# SCH_ERV-controller_2026-01-07.net
KiCad netlist of a schematic drawn in EasyEDA
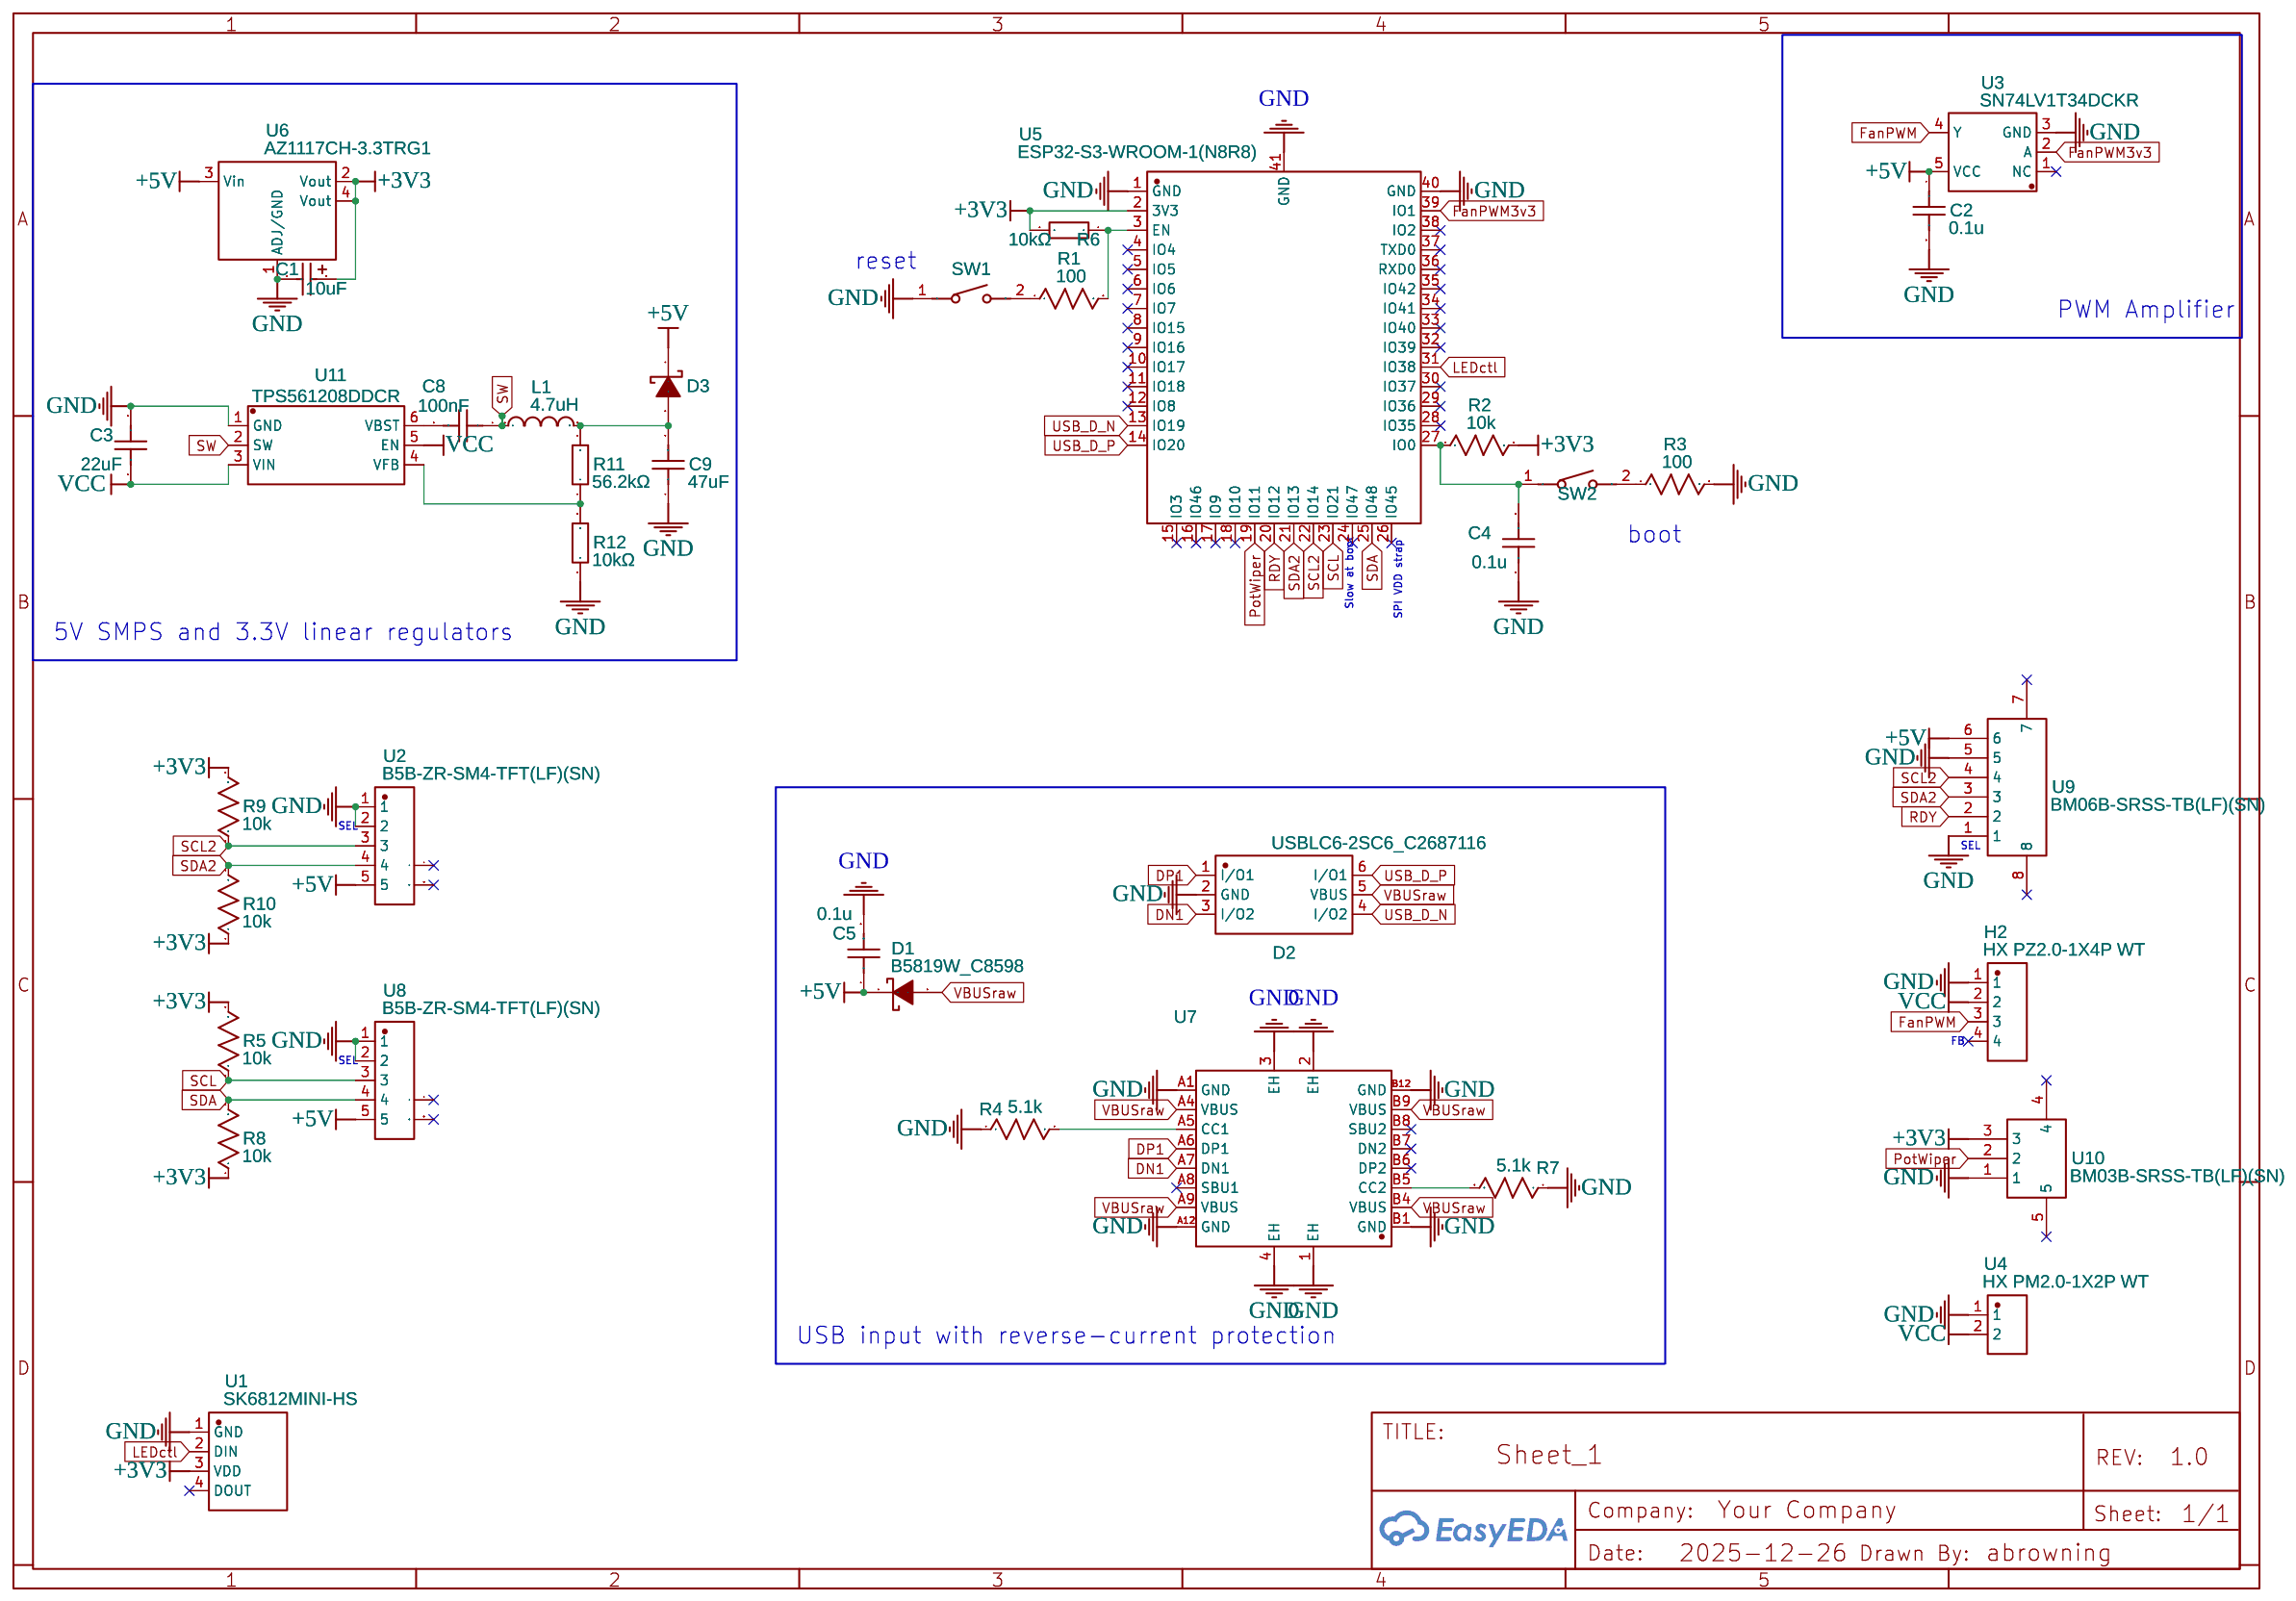
[diagram p0: schematic sheet]

(export (version "E")
  (design (tool "Eeschema 10.0.6"))
  (components
    (comp (ref "C1")
      (value "10uF")
      (fields (field (name "Manufacturer Part") "TAJA106K016RNJ") (field (name "Manufacturer") "Kyocera AVX"))
      (libsource (lib "") (part "TAJA106K016RNJ"))
    )
    (comp (ref "C2") (value "0.1u") (libsource (lib "") (part "C_0603_US")))
    (comp (ref "C3")
      (value "22uF")
      (fields
        (field (name "Manufacturer Part") "CL21A226MAQNNNE")
        (field (name "Manufacturer") "SAMSUNG(三星)")
      )
      (libsource (lib "") (part "CL21A226MAQNNNE"))
    )
    (comp (ref "C4") (value "0.1u") (libsource (lib "") (part "C_0603_US_1")))
    (comp (ref "C5") (value "0.1u") (libsource (lib "") (part "C_0603_US_1")))
    (comp (ref "C8")
      (value "100nF")
      (fields
        (field (name "Manufacturer Part") "CL05B104KO5NNNC")
        (field (name "Manufacturer") "SAMSUNG(三星)")
      )
      (libsource (lib "") (part "CL05B104KO5NNNC"))
    )
    (comp (ref "C9")
      (value "47uF")
      (fields
        (field (name "Manufacturer Part") "CL31A476MPHNNNE")
        (field (name "Manufacturer") "SAMSUNG(三星)")
      )
      (libsource (lib "") (part "CL31A476MPHNNNE"))
    )
    (comp (ref "D1")
      (value "B5819W_C8598")
      (fields (field (name "Manufacturer Part") "B5819W SL") (field (name "Manufacturer") "CJ(江苏长电/长晶)"))
      (libsource (lib "") (part "B5819W_C8598_1"))
    )
    (comp (ref "D2")
      (value "USBLC6-2SC6_C2687116")
      (fields (field (name "Manufacturer Part") "USBLC6-2SC6") (field (name "Manufacturer") "UMW(友台半导体)"))
      (libsource (lib "") (part "USBLC6-2SC6_C2687116"))
    )
    (comp (ref "D3")
      (value "B5819W_C8598")
      (fields (field (name "Manufacturer Part") "B5819W SL") (field (name "Manufacturer") "CJ(江苏长电/长晶)"))
      (libsource (lib "") (part "B5819W_C8598"))
    )
    (comp (ref "H2")
      (value "HX PZ2.0-1X4P WT")
      (fields
        (field (name "Manufacturer Part") "HX PZ2.0-1x4P WT")
        (field (name "Manufacturer") "hanxia(韩下)")
      )
      (libsource (lib "") (part "HX PZ2.0-1X4P WT"))
    )
    (comp (ref "L1")
      (value "4.7uH")
      (fields (field (name "Manufacturer Part") "LQM2HPN4R7MG0L") (field (name "Manufacturer") "muRata(村田)"))
      (libsource (lib "") (part "LQM2HPN4R7MG0L"))
    )
    (comp (ref "R1") (value "100") (libsource (lib "") (part "R_0603_US_1")))
    (comp (ref "R2") (value "10k") (libsource (lib "") (part "R_0603_US_1")))
    (comp (ref "R3") (value "100") (libsource (lib "") (part "R_0603_US_1")))
    (comp (ref "R4") (value "5.1k") (libsource (lib "") (part "R_0603_US_1")))
    (comp (ref "R5") (value "10k") (libsource (lib "") (part "R_0603_US_2")))
    (comp (ref "R6")
      (value "10kΩ")
      (fields
        (field (name "Manufacturer Part") "0402WGF1002TCE")
        (field (name "Manufacturer") "UNI-ROYAL(厚声)")
      )
      (libsource (lib "") (part "0402WGF1002TCE_1"))
    )
    (comp (ref "R7") (value "5.1k") (libsource (lib "") (part "R_0603_US")))
    (comp (ref "R8") (value "10k") (libsource (lib "") (part "R_0603_US_2")))
    (comp (ref "R9") (value "10k") (libsource (lib "") (part "R_0603_US_2")))
    (comp (ref "R10") (value "10k") (libsource (lib "") (part "R_0603_US_2")))
    (comp (ref "R11")
      (value "56.2kΩ")
      (fields (field (name "Manufacturer Part") "RC0402FR-0756K2L") (field (name "Manufacturer") "YAGEO(国巨)"))
      (libsource (lib "") (part "RC0402FR-0756K2L"))
    )
    (comp (ref "R12")
      (value "10kΩ")
      (fields
        (field (name "Manufacturer Part") "0402WGF1002TCE")
        (field (name "Manufacturer") "UNI-ROYAL(厚声)")
      )
      (libsource (lib "") (part "0402WGF1002TCE"))
    )
    (comp (ref "SW1")
      (value "TS-1088-AR02016")
      (fields (field (name "Manufacturer") "XUNPU(讯普)"))
      (libsource (lib "") (part "TS-1088-AR02016"))
    )
    (comp (ref "SW2")
      (value "TS-1088-AR02016")
      (fields (field (name "Manufacturer") "XUNPU(讯普)"))
      (libsource (lib "") (part "TS-1088-AR02016"))
    )
    (comp (ref "U1")
      (value "SK6812MINI-HS")
      (fields (field (name "Manufacturer") "欧思科光电"))
      (libsource (lib "") (part "SK6812MINI-HS"))
    )
    (comp (ref "U2")
      (value "B5B-ZR-SM4-TFT(LF)(SN)")
      (fields (field (name "Manufacturer") "JST"))
      (libsource (lib "") (part "B5B-ZR-SM4-TFT(LF)(SN)"))
    )
    (comp (ref "U3")
      (value "SN74LV1T34DCKR")
      (fields (field (name "Manufacturer") "TI(德州仪器)"))
      (libsource (lib "") (part "SN74LV1T34DCKR"))
    )
    (comp (ref "U4")
      (value "HX PM2.0-1X2P WT")
      (fields
        (field (name "Manufacturer Part") "HX PM2.0-1x2P WT")
        (field (name "Manufacturer") "hanxia(韩下)")
      )
      (libsource (lib "") (part "HX PM2.0-1X2P WT"))
    )
    (comp (ref "U5")
      (value "ESP32-S3-WROOM-1(N8R8)")
      (fields
        (field (name "Manufacturer Part") "ESP32-S3-WROOM-1-N8R8")
        (field (name "Manufacturer") "ESPRESSIF(乐鑫)")
      )
      (libsource (lib "") (part "ESP32-S3-WROOM-1(N8R8)"))
    )
    (comp (ref "U6")
      (value "AZ1117CH-3.3TRG1")
      (fields (field (name "Manufacturer") "DIODES(美台)"))
      (libsource (lib "") (part "AZ1117CH-3.3TRG1"))
    )
    (comp (ref "U7")
      (value "TYPE-C 16P LTH6.8")
      (fields (field (name "Manufacturer") "SHOU HAN(首韩)"))
      (libsource (lib "") (part "TYPE-C 16P LTH6.8"))
    )
    (comp (ref "U8")
      (value "B5B-ZR-SM4-TFT(LF)(SN)")
      (fields (field (name "Manufacturer") "JST"))
      (libsource (lib "") (part "B5B-ZR-SM4-TFT(LF)(SN)"))
    )
    (comp (ref "U9")
      (value "BM06B-SRSS-TB(LF)(SN)")
      (fields (field (name "Manufacturer") "JST"))
      (libsource (lib "") (part "BM06B-SRSS-TB(LF)(SN)"))
    )
    (comp (ref "U10")
      (value "BM03B-SRSS-TB(LF)(SN)")
      (fields (field (name "Manufacturer") "JST"))
      (libsource (lib "") (part "BM03B-SRSS-TB(LF)(SN)"))
    )
    (comp (ref "U11")
      (value "TPS561208DDCR")
      (fields (field (name "Manufacturer") "TI(德州仪器)"))
      (libsource (lib "") (part "TPS561208DDCR"))
    )
  )
  (nets
    (net (code "1") (name "+3V3") (class "Default")
      (node (ref "C1") (pin "1") (pinfunction "1_1") (pintype "input"))
      (node (ref "R10") (pin "1") (pinfunction "1_1") (pintype "unspecified"))
      (node (ref "R2") (pin "2") (pinfunction "2_2") (pintype "unspecified"))
      (node (ref "R5") (pin "2") (pinfunction "2_2") (pintype "unspecified"))
      (node (ref "R6") (pin "2") (pinfunction "2_2") (pintype "input"))
      (node (ref "R8") (pin "1") (pinfunction "1_1") (pintype "unspecified"))
      (node (ref "R9") (pin "2") (pinfunction "2_2") (pintype "unspecified"))
      (node (ref "U1") (pin "3") (pinfunction "VDD_3") (pintype "unspecified"))
      (node (ref "U10") (pin "3") (pinfunction "3_3") (pintype "unspecified"))
      (node (ref "U5") (pin "2") (pinfunction "3V3_2") (pintype "unspecified"))
      (node (ref "U6") (pin "2") (pinfunction "Vout_2") (pintype "unspecified"))
      (node (ref "U6") (pin "4") (pinfunction "Vout_4") (pintype "unspecified"))
    )
    (net (code "2") (name "+5V") (class "Default")
      (node (ref "C2") (pin "1") (pinfunction "1_1") (pintype "unspecified"))
      (node (ref "C5") (pin "1") (pinfunction "1_1") (pintype "unspecified"))
      (node (ref "D1") (pin "1") (pinfunction "-_1") (pintype "unspecified"))
      (node (ref "D3") (pin "1") (pinfunction "-_1") (pintype "unspecified"))
      (node (ref "U2") (pin "5") (pinfunction "5_5") (pintype "unspecified"))
      (node (ref "U3") (pin "5") (pinfunction "VCC_5") (pintype "unspecified"))
      (node (ref "U6") (pin "3") (pinfunction "Vin_3") (pintype "passive"))
      (node (ref "U8") (pin "5") (pinfunction "5_5") (pintype "unspecified"))
      (node (ref "U9") (pin "6") (pinfunction "6_6") (pintype "unspecified"))
    )
    (net (code "3") (name "DN1") (class "Default")
      (node (ref "D2") (pin "3") (pinfunction "I/O2_3") (pintype "unspecified"))
      (node (ref "U7") (pin "A7") (pinfunction "DN1_A7") (pintype "unspecified"))
    )
    (net (code "4") (name "DP1") (class "Default")
      (node (ref "D2") (pin "1") (pinfunction "I/O1_1") (pintype "unspecified"))
      (node (ref "U7") (pin "A6") (pinfunction "DP1_A6") (pintype "unspecified"))
    )
    (net (code "5") (name "FanPWM") (class "Default")
      (node (ref "H2") (pin "3") (pinfunction "3_3") (pintype "unspecified"))
      (node (ref "U3") (pin "4") (pinfunction "Y_4") (pintype "unspecified"))
    )
    (net (code "6") (name "FanPWM3v3") (class "Default")
      (node (ref "U3") (pin "2") (pinfunction "A_2") (pintype "unspecified"))
      (node (ref "U5") (pin "39") (pinfunction "IO1_39") (pintype "unspecified"))
    )
    (net (code "7") (name "GND") (class "Default")
      (node (ref "C1") (pin "2") (pinfunction "2_2") (pintype "input"))
      (node (ref "C2") (pin "2") (pinfunction "2_2") (pintype "unspecified"))
      (node (ref "C3") (pin "2") (pinfunction "2_2") (pintype "unspecified"))
      (node (ref "C4") (pin "1") (pinfunction "1_1") (pintype "unspecified"))
      (node (ref "C5") (pin "2") (pinfunction "2_2") (pintype "unspecified"))
      (node (ref "C9") (pin "1") (pinfunction "1_1") (pintype "unspecified"))
      (node (ref "D2") (pin "2") (pinfunction "GND_2") (pintype "unspecified"))
      (node (ref "H2") (pin "1") (pinfunction "1_1") (pintype "unspecified"))
      (node (ref "R12") (pin "1") (pinfunction "1_1") (pintype "input"))
      (node (ref "R3") (pin "2") (pinfunction "2_2") (pintype "unspecified"))
      (node (ref "R4") (pin "1") (pinfunction "1_1") (pintype "unspecified"))
      (node (ref "R7") (pin "1") (pinfunction "1_1") (pintype "unspecified"))
      (node (ref "SW1") (pin "1") (pinfunction "1_1") (pintype "unspecified"))
      (node (ref "U1") (pin "1") (pinfunction "GND_1") (pintype "unspecified"))
      (node (ref "U10") (pin "1") (pinfunction "1_1") (pintype "unspecified"))
      (node (ref "U11") (pin "1") (pinfunction "GND_1") (pintype "unspecified"))
      (node (ref "U2") (pin "1") (pinfunction "1_1") (pintype "unspecified"))
      (node (ref "U2") (pin "2") (pinfunction "2_2") (pintype "unspecified"))
      (node (ref "U3") (pin "3") (pinfunction "GND_3") (pintype "unspecified"))
      (node (ref "U4") (pin "1") (pinfunction "1_1") (pintype "unspecified"))
      (node (ref "U5") (pin "1") (pinfunction "GND_1") (pintype "unspecified"))
      (node (ref "U5") (pin "40") (pinfunction "GND_40") (pintype "unspecified"))
      (node (ref "U5") (pin "41") (pinfunction "GND_41") (pintype "unspecified"))
      (node (ref "U6") (pin "1") (pinfunction "ADJ/GND_1") (pintype "unspecified"))
      (node (ref "U7") (pin "1") (pinfunction "EH_1") (pintype "unspecified"))
      (node (ref "U7") (pin "2") (pinfunction "EH_2") (pintype "unspecified"))
      (node (ref "U7") (pin "3") (pinfunction "EH_3") (pintype "unspecified"))
      (node (ref "U7") (pin "4") (pinfunction "EH_4") (pintype "unspecified"))
      (node (ref "U7") (pin "A1") (pinfunction "GND_A1") (pintype "unspecified"))
      (node (ref "U7") (pin "A12") (pinfunction "GND_A12") (pintype "unspecified"))
      (node (ref "U7") (pin "B1") (pinfunction "GND_B1") (pintype "unspecified"))
      (node (ref "U7") (pin "B12") (pinfunction "GND_B12") (pintype "unspecified"))
      (node (ref "U8") (pin "1") (pinfunction "1_1") (pintype "unspecified"))
      (node (ref "U8") (pin "2") (pinfunction "2_2") (pintype "unspecified"))
      (node (ref "U9") (pin "1") (pinfunction "1_1") (pintype "unspecified"))
      (node (ref "U9") (pin "5") (pinfunction "5_5") (pintype "unspecified"))
    )
    (net (code "8") (name "LEDctl") (class "Default")
      (node (ref "U1") (pin "2") (pinfunction "DIN_2") (pintype "unspecified"))
      (node (ref "U5") (pin "31") (pinfunction "IO38_31") (pintype "unspecified"))
    )
    (net (code "9") (name "Net-(D3-+)") (class "Default")
      (node (ref "C9") (pin "2") (pinfunction "2_2") (pintype "unspecified"))
      (node (ref "D3") (pin "2") (pinfunction "+_2") (pintype "unspecified"))
      (node (ref "L1") (pin "2") (pinfunction "2_2") (pintype "unspecified"))
      (node (ref "R11") (pin "2") (pinfunction "2_2") (pintype "unspecified"))
    )
    (net (code "10") (name "Net-(R1-Pad1)") (class "Default")
      (node (ref "R1") (pin "1") (pinfunction "1_1") (pintype "unspecified"))
      (node (ref "SW1") (pin "2") (pinfunction "2_2") (pintype "unspecified"))
    )
    (net (code "11") (name "Net-(R3-Pad1)") (class "Default")
      (node (ref "R3") (pin "1") (pinfunction "1_1") (pintype "unspecified"))
      (node (ref "SW2") (pin "2") (pinfunction "2_2") (pintype "unspecified"))
    )
    (net (code "12") (name "Net-(U5-EN)") (class "Default")
      (node (ref "R1") (pin "2") (pinfunction "2_2") (pintype "unspecified"))
      (node (ref "R6") (pin "1") (pinfunction "1_1") (pintype "input"))
      (node (ref "U5") (pin "3") (pinfunction "EN_3") (pintype "unspecified"))
    )
    (net (code "13") (name "Net-(U5-IO0)") (class "Default")
      (node (ref "C4") (pin "2") (pinfunction "2_2") (pintype "unspecified"))
      (node (ref "R2") (pin "1") (pinfunction "1_1") (pintype "unspecified"))
      (node (ref "SW2") (pin "1") (pinfunction "1_1") (pintype "unspecified"))
      (node (ref "U5") (pin "27") (pinfunction "IO0_27") (pintype "unspecified"))
    )
    (net (code "14") (name "Net-(U7-CC1)") (class "Default")
      (node (ref "R4") (pin "2") (pinfunction "2_2") (pintype "unspecified"))
      (node (ref "U7") (pin "A5") (pinfunction "CC1_A5") (pintype "unspecified"))
    )
    (net (code "15") (name "Net-(U7-CC2)") (class "Default")
      (node (ref "R7") (pin "2") (pinfunction "2_2") (pintype "unspecified"))
      (node (ref "U7") (pin "B5") (pinfunction "CC2_B5") (pintype "unspecified"))
    )
    (net (code "16") (name "Net-(U11-VBST)") (class "Default")
      (node (ref "C8") (pin "2") (pinfunction "2_2") (pintype "unspecified"))
      (node (ref "U11") (pin "6") (pinfunction "VBST_6") (pintype "unspecified"))
    )
    (net (code "17") (name "Net-(U11-VFB)") (class "Default")
      (node (ref "R11") (pin "1") (pinfunction "1_1") (pintype "unspecified"))
      (node (ref "R12") (pin "2") (pinfunction "2_2") (pintype "input"))
      (node (ref "U11") (pin "4") (pinfunction "VFB_4") (pintype "unspecified"))
    )
    (net (code "18") (name "PotWiper") (class "Default")
      (node (ref "U10") (pin "2") (pinfunction "2_2") (pintype "unspecified"))
      (node (ref "U5") (pin "19") (pinfunction "IO11_19") (pintype "unspecified"))
    )
    (net (code "19") (name "RDY") (class "Default")
      (node (ref "U5") (pin "20") (pinfunction "IO12_20") (pintype "unspecified"))
      (node (ref "U9") (pin "2") (pinfunction "2_2") (pintype "unspecified"))
    )
    (net (code "20") (name "SCL") (class "Default")
      (node (ref "R5") (pin "1") (pinfunction "1_1") (pintype "unspecified"))
      (node (ref "U5") (pin "23") (pinfunction "IO21_23") (pintype "unspecified"))
      (node (ref "U8") (pin "3") (pinfunction "3_3") (pintype "unspecified"))
    )
    (net (code "21") (name "SCL2") (class "Default")
      (node (ref "R9") (pin "1") (pinfunction "1_1") (pintype "unspecified"))
      (node (ref "U2") (pin "3") (pinfunction "3_3") (pintype "unspecified"))
      (node (ref "U5") (pin "22") (pinfunction "IO14_22") (pintype "unspecified"))
      (node (ref "U9") (pin "4") (pinfunction "4_4") (pintype "unspecified"))
    )
    (net (code "22") (name "SDA") (class "Default")
      (node (ref "R8") (pin "2") (pinfunction "2_2") (pintype "unspecified"))
      (node (ref "U5") (pin "25") (pinfunction "IO48_25") (pintype "unspecified"))
      (node (ref "U8") (pin "4") (pinfunction "4_4") (pintype "unspecified"))
    )
    (net (code "23") (name "SDA2") (class "Default")
      (node (ref "R10") (pin "2") (pinfunction "2_2") (pintype "unspecified"))
      (node (ref "U2") (pin "4") (pinfunction "4_4") (pintype "unspecified"))
      (node (ref "U5") (pin "21") (pinfunction "IO13_21") (pintype "unspecified"))
      (node (ref "U9") (pin "3") (pinfunction "3_3") (pintype "unspecified"))
    )
    (net (code "24") (name "SW") (class "Default")
      (node (ref "C8") (pin "1") (pinfunction "1_1") (pintype "unspecified"))
      (node (ref "L1") (pin "1") (pinfunction "1_1") (pintype "unspecified"))
      (node (ref "U11") (pin "2") (pinfunction "SW_2") (pintype "unspecified"))
    )
    (net (code "25") (name "USB_D_N") (class "Default")
      (node (ref "D2") (pin "4") (pinfunction "I/O2_4") (pintype "unspecified"))
      (node (ref "U5") (pin "13") (pinfunction "IO19_13") (pintype "unspecified"))
    )
    (net (code "26") (name "USB_D_P") (class "Default")
      (node (ref "D2") (pin "6") (pinfunction "I/O1_6") (pintype "unspecified"))
      (node (ref "U5") (pin "14") (pinfunction "IO20_14") (pintype "unspecified"))
    )
    (net (code "27") (name "VBUSraw") (class "Default")
      (node (ref "D1") (pin "2") (pinfunction "+_2") (pintype "unspecified"))
      (node (ref "D2") (pin "5") (pinfunction "VBUS_5") (pintype "unspecified"))
      (node (ref "U7") (pin "A4") (pinfunction "VBUS_A4") (pintype "unspecified"))
      (node (ref "U7") (pin "A9") (pinfunction "VBUS_A9") (pintype "unspecified"))
      (node (ref "U7") (pin "B4") (pinfunction "VBUS_B4") (pintype "unspecified"))
      (node (ref "U7") (pin "B9") (pinfunction "VBUS_B9") (pintype "unspecified"))
    )
    (net (code "28") (name "VCC") (class "Default")
      (node (ref "C3") (pin "1") (pinfunction "1_1") (pintype "unspecified"))
      (node (ref "H2") (pin "2") (pinfunction "2_2") (pintype "unspecified"))
      (node (ref "U11") (pin "3") (pinfunction "VIN_3") (pintype "unspecified"))
      (node (ref "U11") (pin "5") (pinfunction "EN_5") (pintype "unspecified"))
      (node (ref "U4") (pin "2") (pinfunction "2_2") (pintype "unspecified"))
    )
    (net (code "29") (name "unconnected-(H2-Pad4)") (class "Default")
      (node (ref "H2") (pin "4") (pinfunction "4_4") (pintype "unspecified+no_connect"))
    )
    (net (code "30") (name "unconnected-(U1-DOUT-Pad4)") (class "Default")
      (node (ref "U1") (pin "4") (pinfunction "DOUT_4") (pintype "unspecified+no_connect"))
    )
    (net (code "31") (name "unconnected-(U2-Pad6)") (class "Default")
      (node (ref "U2") (pin "6") (pinfunction "6_6") (pintype "unspecified+no_connect"))
    )
    (net (code "32") (name "unconnected-(U2-Pad7)") (class "Default")
      (node (ref "U2") (pin "7") (pinfunction "7_7") (pintype "unspecified+no_connect"))
    )
    (net (code "33") (name "unconnected-(U3-NC-Pad1)") (class "Default")
      (node (ref "U3") (pin "1") (pinfunction "NC_1") (pintype "unspecified+no_connect"))
    )
    (net (code "34") (name "unconnected-(U5-IO2-Pad38)") (class "Default")
      (node (ref "U5") (pin "38") (pinfunction "IO2_38") (pintype "unspecified+no_connect"))
    )
    (net (code "35") (name "unconnected-(U5-IO3-Pad15)") (class "Default")
      (node (ref "U5") (pin "15") (pinfunction "IO3_15") (pintype "unspecified+no_connect"))
    )
    (net (code "36") (name "unconnected-(U5-IO4-Pad4)") (class "Default")
      (node (ref "U5") (pin "4") (pinfunction "IO4_4") (pintype "unspecified+no_connect"))
    )
    (net (code "37") (name "unconnected-(U5-IO5-Pad5)") (class "Default")
      (node (ref "U5") (pin "5") (pinfunction "IO5_5") (pintype "unspecified+no_connect"))
    )
    (net (code "38") (name "unconnected-(U5-IO6-Pad6)") (class "Default")
      (node (ref "U5") (pin "6") (pinfunction "IO6_6") (pintype "unspecified+no_connect"))
    )
    (net (code "39") (name "unconnected-(U5-IO7-Pad7)") (class "Default")
      (node (ref "U5") (pin "7") (pinfunction "IO7_7") (pintype "unspecified+no_connect"))
    )
    (net (code "40") (name "unconnected-(U5-IO8-Pad12)") (class "Default")
      (node (ref "U5") (pin "12") (pinfunction "IO8_12") (pintype "unspecified+no_connect"))
    )
    (net (code "41") (name "unconnected-(U5-IO9-Pad17)") (class "Default")
      (node (ref "U5") (pin "17") (pinfunction "IO9_17") (pintype "unspecified+no_connect"))
    )
    (net (code "42") (name "unconnected-(U5-IO10-Pad18)") (class "Default")
      (node (ref "U5") (pin "18") (pinfunction "IO10_18") (pintype "unspecified+no_connect"))
    )
    (net (code "43") (name "unconnected-(U5-IO15-Pad8)") (class "Default")
      (node (ref "U5") (pin "8") (pinfunction "IO15_8") (pintype "unspecified+no_connect"))
    )
    (net (code "44") (name "unconnected-(U5-IO16-Pad9)") (class "Default")
      (node (ref "U5") (pin "9") (pinfunction "IO16_9") (pintype "unspecified+no_connect"))
    )
    (net (code "45") (name "unconnected-(U5-IO17-Pad10)") (class "Default")
      (node (ref "U5") (pin "10") (pinfunction "IO17_10") (pintype "unspecified+no_connect"))
    )
    (net (code "46") (name "unconnected-(U5-IO18-Pad11)") (class "Default")
      (node (ref "U5") (pin "11") (pinfunction "IO18_11") (pintype "unspecified+no_connect"))
    )
    (net (code "47") (name "unconnected-(U5-IO35-Pad28)") (class "Default")
      (node (ref "U5") (pin "28") (pinfunction "IO35_28") (pintype "unspecified+no_connect"))
    )
    (net (code "48") (name "unconnected-(U5-IO36-Pad29)") (class "Default")
      (node (ref "U5") (pin "29") (pinfunction "IO36_29") (pintype "unspecified+no_connect"))
    )
    (net (code "49") (name "unconnected-(U5-IO37-Pad30)") (class "Default")
      (node (ref "U5") (pin "30") (pinfunction "IO37_30") (pintype "unspecified+no_connect"))
    )
    (net (code "50") (name "unconnected-(U5-IO39-Pad32)") (class "Default")
      (node (ref "U5") (pin "32") (pinfunction "IO39_32") (pintype "unspecified+no_connect"))
    )
    (net (code "51") (name "unconnected-(U5-IO40-Pad33)") (class "Default")
      (node (ref "U5") (pin "33") (pinfunction "IO40_33") (pintype "unspecified+no_connect"))
    )
    (net (code "52") (name "unconnected-(U5-IO41-Pad34)") (class "Default")
      (node (ref "U5") (pin "34") (pinfunction "IO41_34") (pintype "unspecified+no_connect"))
    )
    (net (code "53") (name "unconnected-(U5-IO42-Pad35)") (class "Default")
      (node (ref "U5") (pin "35") (pinfunction "IO42_35") (pintype "unspecified+no_connect"))
    )
    (net (code "54") (name "unconnected-(U5-IO45-Pad26)") (class "Default")
      (node (ref "U5") (pin "26") (pinfunction "IO45_26") (pintype "unspecified+no_connect"))
    )
    (net (code "55") (name "unconnected-(U5-IO46-Pad16)") (class "Default")
      (node (ref "U5") (pin "16") (pinfunction "IO46_16") (pintype "unspecified+no_connect"))
    )
    (net (code "56") (name "unconnected-(U5-IO47-Pad24)") (class "Default")
      (node (ref "U5") (pin "24") (pinfunction "IO47_24") (pintype "unspecified+no_connect"))
    )
    (net (code "57") (name "unconnected-(U5-RXD0-Pad36)") (class "Default")
      (node (ref "U5") (pin "36") (pinfunction "RXD0_36") (pintype "unspecified+no_connect"))
    )
    (net (code "58") (name "unconnected-(U5-TXD0-Pad37)") (class "Default")
      (node (ref "U5") (pin "37") (pinfunction "TXD0_37") (pintype "unspecified+no_connect"))
    )
    (net (code "59") (name "unconnected-(U7-DN2-PadB7)") (class "Default")
      (node (ref "U7") (pin "B7") (pinfunction "DN2_B7") (pintype "unspecified+no_connect"))
    )
    (net (code "60") (name "unconnected-(U7-DP2-PadB6)") (class "Default")
      (node (ref "U7") (pin "B6") (pinfunction "DP2_B6") (pintype "unspecified+no_connect"))
    )
    (net (code "61") (name "unconnected-(U7-SBU1-PadA8)") (class "Default")
      (node (ref "U7") (pin "A8") (pinfunction "SBU1_A8") (pintype "unspecified+no_connect"))
    )
    (net (code "62") (name "unconnected-(U7-SBU2-PadB8)") (class "Default")
      (node (ref "U7") (pin "B8") (pinfunction "SBU2_B8") (pintype "unspecified+no_connect"))
    )
    (net (code "63") (name "unconnected-(U8-Pad6)") (class "Default")
      (node (ref "U8") (pin "6") (pinfunction "6_6") (pintype "unspecified+no_connect"))
    )
    (net (code "64") (name "unconnected-(U8-Pad7)") (class "Default")
      (node (ref "U8") (pin "7") (pinfunction "7_7") (pintype "unspecified+no_connect"))
    )
    (net (code "65") (name "unconnected-(U9-Pad7)") (class "Default")
      (node (ref "U9") (pin "7") (pinfunction "7_7") (pintype "unspecified+no_connect"))
    )
    (net (code "66") (name "unconnected-(U9-Pad8)") (class "Default")
      (node (ref "U9") (pin "8") (pinfunction "8_8") (pintype "unspecified+no_connect"))
    )
    (net (code "67") (name "unconnected-(U10-Pad4)") (class "Default")
      (node (ref "U10") (pin "4") (pinfunction "4_4") (pintype "unspecified+no_connect"))
    )
    (net (code "68") (name "unconnected-(U10-Pad5)") (class "Default")
      (node (ref "U10") (pin "5") (pinfunction "5_5") (pintype "unspecified+no_connect"))
    )
  )
)
